# fallBz2.net
KiCad netlist of a schematic drawn in EAGLE
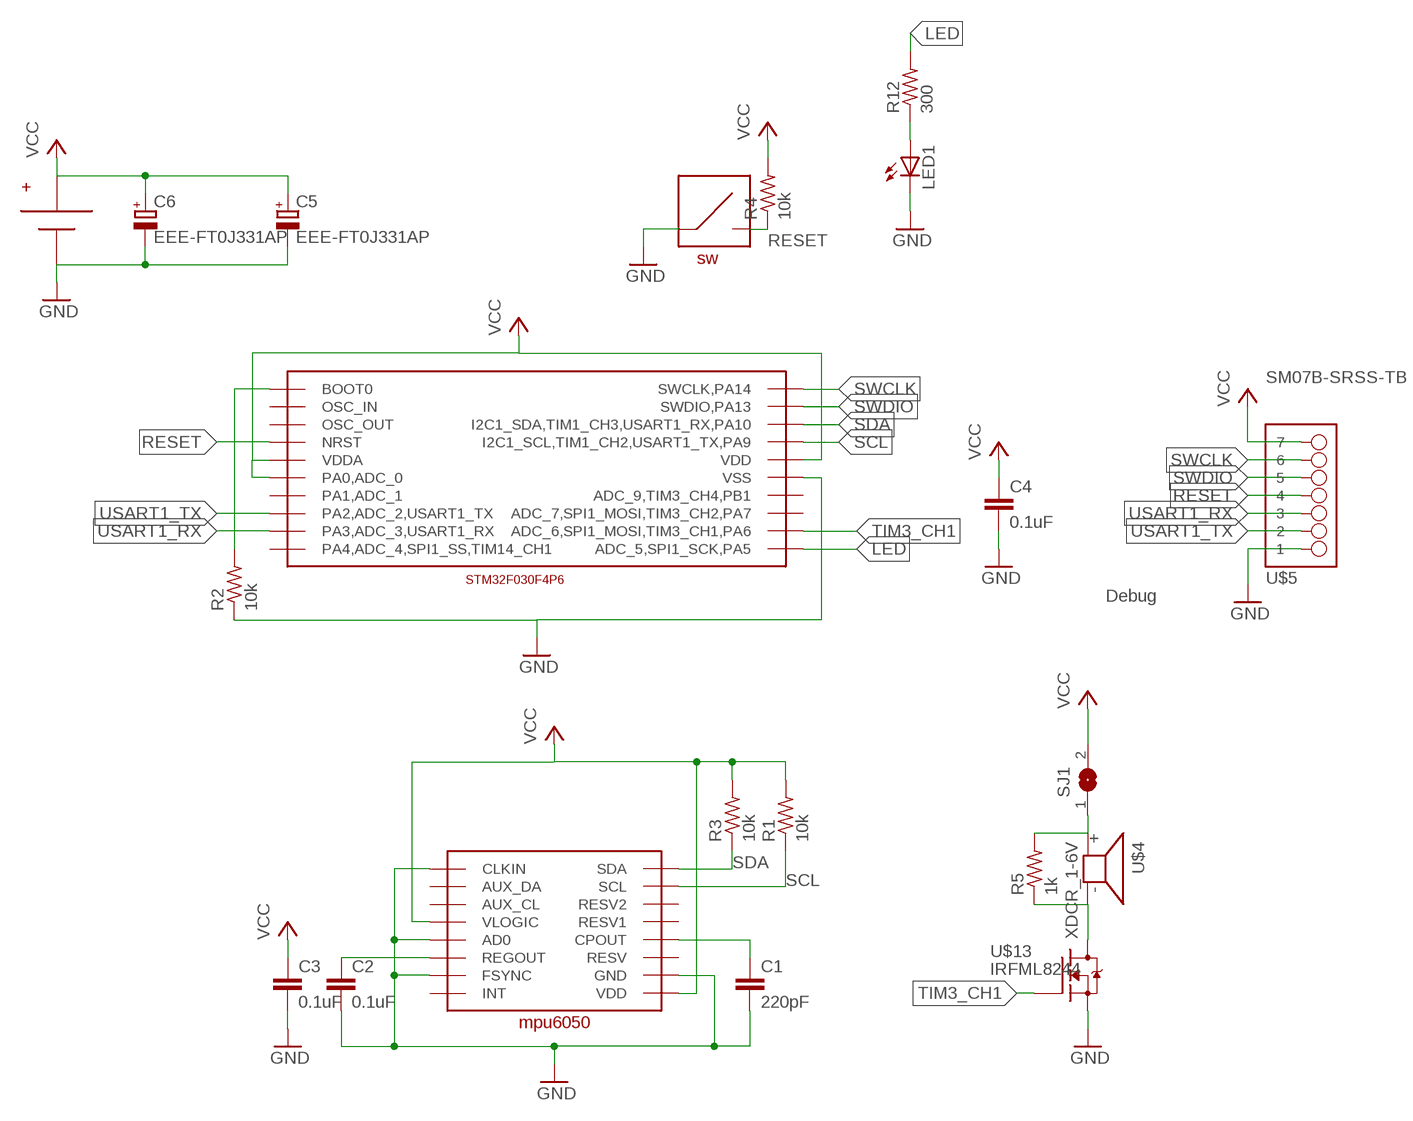
[diagram p0: schematic, sheet 1]

(export (version "E")
  (design (tool "Eeschema 10.0.6"))
  (components
    (comp (ref "C1")
      (value "220pF")
      (footprint "eagle-import:C0603K")
      (libsource (lib "eagle-import") (part "C-EUC0603K"))
    )
    (comp (ref "C2")
      (value "0.1uF")
      (footprint "eagle-import:C0603K")
      (libsource (lib "eagle-import") (part "C-EUC0603K"))
    )
    (comp (ref "C3")
      (value "0.1uF")
      (footprint "eagle-import:C0603K")
      (libsource (lib "eagle-import") (part "C-EUC0603K"))
    )
    (comp (ref "C4")
      (value "0.1uF")
      (footprint "eagle-import:C0603K")
      (libsource (lib "eagle-import") (part "C-EUC0603K"))
    )
    (comp (ref "C5")
      (value "EEE-FT0J331AP")
      (footprint "eagle-import:153CLV-0605")
      (libsource (lib "eagle-import") (part "CPOL-EU153CLV-0605"))
    )
    (comp (ref "C6")
      (value "EEE-FT0J331AP")
      (footprint "eagle-import:153CLV-0605")
      (libsource (lib "eagle-import") (part "CPOL-EU153CLV-0605"))
    )
    (comp (ref "LED1")
      (value "LEDCHIP-LED0603")
      (footprint "eagle-import:CHIP-LED0603")
      (libsource (lib "eagle-import") (part "LEDCHIP-LED0603"))
    )
    (comp (ref "R1")
      (value "10k")
      (footprint "eagle-import:R0603")
      (libsource (lib "eagle-import") (part "R-US_R0603"))
    )
    (comp (ref "R2")
      (value "10k")
      (footprint "eagle-import:R0603")
      (libsource (lib "eagle-import") (part "R-US_R0603"))
    )
    (comp (ref "R3")
      (value "10k")
      (footprint "eagle-import:R0603")
      (libsource (lib "eagle-import") (part "R-US_R0603"))
    )
    (comp (ref "R4")
      (value "10k")
      (footprint "eagle-import:R0603")
      (libsource (lib "eagle-import") (part "R-US_R0603"))
    )
    (comp (ref "R5")
      (value "1k")
      (footprint "eagle-import:R0603")
      (libsource (lib "eagle-import") (part "R-US_R0603"))
    )
    (comp (ref "R12")
      (value "300")
      (footprint "eagle-import:R0603")
      (libsource (lib "eagle-import") (part "R-US_R0603"))
    )
    (comp (ref "SJ1") (value "SJ") (footprint "eagle-import:SJ") (libsource (lib "eagle-import") (part "SJ")))
    (comp (ref "U$1")
      (value "STM-TSSOP20")
      (footprint "eagle-import:STM-TSSOP20")
      (libsource (lib "eagle-import") (part "STM-TSSOP20"))
    )
    (comp (ref "U$2")
      (value "BAT_BK-912")
      (footprint "eagle-import:BAT_BK-912")
      (libsource (lib "eagle-import") (part "BAT_BK-912"))
    )
    (comp (ref "U$3")
      (value "MPU6050")
      (footprint "eagle-import:MPU6050")
      (libsource (lib "eagle-import") (part "MPU6050"))
    )
    (comp (ref "U$4")
      (value "XDCR_1-6V")
      (footprint "eagle-import:XDCR_1-6V")
      (libsource (lib "eagle-import") (part "XDCR_1-6V"))
    )
    (comp (ref "U$5")
      (value "SM07B-SRSS-TB")
      (footprint "eagle-import:SM07B-SRSS-TB")
      (libsource (lib "eagle-import") (part "SM07B-SRSS-TB"))
    )
    (comp (ref "U$7")
      (value "KMT071-NGJ-LHS")
      (footprint "eagle-import:KMT071-NGJ-LHS")
      (libsource (lib "eagle-import") (part "KMT071-NGJ-LHS"))
    )
    (comp (ref "U$13")
      (value "IRFML8244")
      (footprint "eagle-import:SOT23")
      (libsource (lib "eagle-import") (part "IRFML8244"))
    )
  )
  (nets
    (net (code "1") (name "GND") (class "Default")
      (node (ref "C1") (pin "2") (pinfunction "2_2") (pintype "passive"))
      (node (ref "C2") (pin "2") (pinfunction "2_2") (pintype "passive"))
      (node (ref "C3") (pin "2") (pinfunction "2_2") (pintype "passive"))
      (node (ref "C4") (pin "2") (pinfunction "2_2") (pintype "passive"))
      (node (ref "C5") (pin "-") (pinfunction "-_-") (pintype "passive"))
      (node (ref "C6") (pin "-") (pinfunction "-_-") (pintype "passive"))
      (node (ref "LED1") (pin "C") (pinfunction "C_C") (pintype "passive"))
      (node (ref "R2") (pin "1") (pinfunction "1_1") (pintype "passive"))
      (node (ref "U$1") (pin "P$15") (pinfunction "VSS_P$15") (pintype "bidirectional"))
      (node (ref "U$13") (pin "2") (pinfunction "S_2") (pintype "passive"))
      (node (ref "U$2") (pin "MINUS") (pinfunction "MINSU_MINUS") (pintype "bidirectional"))
      (node (ref "U$3") (pin "AD0") (pinfunction "AD0_AD0") (pintype "bidirectional"))
      (node (ref "U$3") (pin "CLKIN") (pinfunction "CLKIN_CLKIN") (pintype "bidirectional"))
      (node (ref "U$3") (pin "FSYNC") (pinfunction "FSYNC_FSYNC") (pintype "bidirectional"))
      (node (ref "U$3") (pin "GND") (pinfunction "GND_GND") (pintype "bidirectional"))
      (node (ref "U$5") (pin "P$1") (pinfunction "1_P$1") (pintype "bidirectional"))
      (node (ref "U$7") (pin "SW0") (pinfunction "P$1_SW0") (pintype "bidirectional"))
      (node (ref "U$7") (pin "SW00") (pinfunction "P$1_SW00") (pintype "bidirectional"))
    )
    (net (code "2") (name "LED") (class "Default")
      (node (ref "R12") (pin "2") (pinfunction "2_2") (pintype "passive"))
      (node (ref "U$1") (pin "P$11") (pinfunction "ADC_5,SPI1_SCK,PA5_P$11") (pintype "bidirectional"))
    )
    (net (code "3") (name "Net-(C1-Pad1)") (class "Default")
      (node (ref "C1") (pin "1") (pinfunction "1_1") (pintype "passive"))
      (node (ref "U$3") (pin "CPOUT") (pinfunction "CPOUT_CPOUT") (pintype "bidirectional"))
    )
    (net (code "4") (name "Net-(C2-Pad1)") (class "Default")
      (node (ref "C2") (pin "1") (pinfunction "1_1") (pintype "passive"))
      (node (ref "U$3") (pin "REGOUT") (pinfunction "REGOUT_REGOUT") (pintype "bidirectional"))
    )
    (net (code "5") (name "Net-(LED1-PadA)") (class "Default")
      (node (ref "LED1") (pin "A") (pinfunction "A_A") (pintype "passive"))
      (node (ref "R12") (pin "1") (pinfunction "1_1") (pintype "passive"))
    )
    (net (code "6") (name "Net-(R5-Pad2)") (class "Default")
      (node (ref "R5") (pin "2") (pinfunction "2_2") (pintype "passive"))
      (node (ref "SJ1") (pin "1") (pinfunction "1_1") (pintype "passive"))
      (node (ref "U$4") (pin "PLUS") (pinfunction "PLUS_PLUS") (pintype "passive"))
    )
    (net (code "7") (name "Net-(U$1-BOOT0)") (class "Default")
      (node (ref "R2") (pin "2") (pinfunction "2_2") (pintype "passive"))
      (node (ref "U$1") (pin "P$1") (pinfunction "BOOT0_P$1") (pintype "bidirectional"))
    )
    (net (code "8") (name "Net-(U$13-D)") (class "Default")
      (node (ref "R5") (pin "1") (pinfunction "1_1") (pintype "passive"))
      (node (ref "U$13") (pin "3") (pinfunction "D_3") (pintype "passive"))
      (node (ref "U$4") (pin "MINUS") (pinfunction "2_MINUS") (pintype "passive"))
    )
    (net (code "9") (name "RESET") (class "Default")
      (node (ref "R4") (pin "1") (pinfunction "1_1") (pintype "passive"))
      (node (ref "U$1") (pin "P$4") (pinfunction "NRST_P$4") (pintype "bidirectional"))
      (node (ref "U$5") (pin "P$4") (pinfunction "4_P$4") (pintype "bidirectional"))
      (node (ref "U$7") (pin "SW1") (pinfunction "P$2_SW1") (pintype "bidirectional"))
      (node (ref "U$7") (pin "SW11") (pinfunction "P$2_SW11") (pintype "bidirectional"))
    )
    (net (code "10") (name "SCL") (class "Default")
      (node (ref "R1") (pin "1") (pinfunction "1_1") (pintype "passive"))
      (node (ref "U$1") (pin "P$17") (pinfunction "I2C1_SCL,TIM1_CH2,USART1_TX,PA9_P$17") (pintype "bidirectional"))
      (node (ref "U$3") (pin "SCL") (pinfunction "SCL_SCL") (pintype "bidirectional"))
    )
    (net (code "11") (name "SDA") (class "Default")
      (node (ref "R3") (pin "1") (pinfunction "1_1") (pintype "passive"))
      (node (ref "U$1") (pin "P$18") (pinfunction "I2C1_SDA,TIM1_CH3,USART1_RX,PA10_P$18") (pintype "bidirectional"))
      (node (ref "U$3") (pin "SDA") (pinfunction "SDA_SDA") (pintype "bidirectional"))
    )
    (net (code "12") (name "SWCLK") (class "Default")
      (node (ref "U$1") (pin "P$20") (pinfunction "SWCLK,PA14_P$20") (pintype "bidirectional"))
      (node (ref "U$5") (pin "P$6") (pinfunction "6_P$6") (pintype "bidirectional"))
    )
    (net (code "13") (name "SWDIO") (class "Default")
      (node (ref "U$1") (pin "P$19") (pinfunction "SWDIO,PA13_P$19") (pintype "bidirectional"))
      (node (ref "U$5") (pin "P$5") (pinfunction "5_P$5") (pintype "bidirectional"))
    )
    (net (code "14") (name "TIM3_CH1") (class "Default")
      (node (ref "U$1") (pin "P$12") (pinfunction "ADC_6,SPI1_MOSI,TIM3_CH1,PA6_P$12") (pintype "bidirectional"))
      (node (ref "U$13") (pin "1") (pinfunction "G_1") (pintype "passive"))
    )
    (net (code "15") (name "USART1_RX") (class "Default")
      (node (ref "U$1") (pin "P$9") (pinfunction "PA3,ADC_3,USART1_RX_P$9") (pintype "bidirectional"))
      (node (ref "U$5") (pin "P$3") (pinfunction "3_P$3") (pintype "bidirectional"))
    )
    (net (code "16") (name "USART1_TX") (class "Default")
      (node (ref "U$1") (pin "P$8") (pinfunction "PA2,ADC_2,USART1_TX_P$8") (pintype "bidirectional"))
      (node (ref "U$5") (pin "P$2") (pinfunction "2_P$2") (pintype "bidirectional"))
    )
    (net (code "17") (name "VCC") (class "Default")
      (node (ref "C3") (pin "1") (pinfunction "1_1") (pintype "passive"))
      (node (ref "C4") (pin "1") (pinfunction "1_1") (pintype "passive"))
      (node (ref "C5") (pin "+") (pinfunction "+_+") (pintype "passive"))
      (node (ref "C6") (pin "+") (pinfunction "+_+") (pintype "passive"))
      (node (ref "R1") (pin "2") (pinfunction "2_2") (pintype "passive"))
      (node (ref "R3") (pin "2") (pinfunction "2_2") (pintype "passive"))
      (node (ref "R4") (pin "2") (pinfunction "2_2") (pintype "passive"))
      (node (ref "SJ1") (pin "2") (pinfunction "2_2") (pintype "passive"))
      (node (ref "U$1") (pin "P$16") (pinfunction "VDD_P$16") (pintype "bidirectional"))
      (node (ref "U$1") (pin "P$5") (pinfunction "VDDA_P$5") (pintype "bidirectional"))
      (node (ref "U$1") (pin "P$6") (pinfunction "PA0,ADC_0_P$6") (pintype "bidirectional"))
      (node (ref "U$2") (pin "P$1") (pinfunction "PLUS_P$1") (pintype "bidirectional"))
      (node (ref "U$2") (pin "P$2") (pinfunction "PLUS_P$2") (pintype "bidirectional"))
      (node (ref "U$3") (pin "VDD") (pinfunction "VDD_VDD") (pintype "bidirectional"))
      (node (ref "U$3") (pin "VLOGIC") (pinfunction "VLOGIC_VLOGIC") (pintype "bidirectional"))
      (node (ref "U$5") (pin "P$7") (pinfunction "7_P$7") (pintype "bidirectional"))
    )
    (net (code "18") (name "unconnected-(U$1-ADC_7,SPI1_MOSI,TIM3_CH2,PA7-PadP$13)") (class "Default")
      (node (ref "U$1") (pin "P$13") (pinfunction "ADC_7,SPI1_MOSI,TIM3_CH2,PA7_P$13") (pintype "bidirectional"))
    )
    (net (code "19") (name "unconnected-(U$1-ADC_9,TIM3_CH4,PB1-PadP$14)") (class "Default")
      (node (ref "U$1") (pin "P$14") (pinfunction "ADC_9,TIM3_CH4,PB1_P$14") (pintype "bidirectional"))
    )
    (net (code "20") (name "unconnected-(U$1-OSC_IN-PadP$2)") (class "Default")
      (node (ref "U$1") (pin "P$2") (pinfunction "OSC_IN_P$2") (pintype "bidirectional"))
    )
    (net (code "21") (name "unconnected-(U$1-OSC_OUT-PadP$3)") (class "Default")
      (node (ref "U$1") (pin "P$3") (pinfunction "OSC_OUT_P$3") (pintype "bidirectional"))
    )
    (net (code "22") (name "unconnected-(U$1-PA1,ADC_1-PadP$7)") (class "Default")
      (node (ref "U$1") (pin "P$7") (pinfunction "PA1,ADC_1_P$7") (pintype "bidirectional"))
    )
    (net (code "23") (name "unconnected-(U$1-PA4,ADC_4,SPI1_SS,TIM14_CH1-PadP$10)") (class "Default")
      (node (ref "U$1") (pin "P$10") (pinfunction "PA4,ADC_4,SPI1_SS,TIM14_CH1_P$10") (pintype "bidirectional"))
    )
    (net (code "24") (name "unconnected-(U$3-PadAUX_CL)") (class "Default")
      (node (ref "U$3") (pin "AUX_CL") (pinfunction "AUX_CL_AUX_CL") (pintype "bidirectional"))
    )
    (net (code "25") (name "unconnected-(U$3-PadAUX_DA)") (class "Default")
      (node (ref "U$3") (pin "AUX_DA") (pinfunction "AUX_DA_AUX_DA") (pintype "bidirectional"))
    )
    (net (code "26") (name "unconnected-(U$3-PadINT)") (class "Default")
      (node (ref "U$3") (pin "INT") (pinfunction "INT_INT") (pintype "bidirectional"))
    )
    (net (code "27") (name "unconnected-(U$3-PadRESV)") (class "Default")
      (node (ref "U$3") (pin "RESV") (pinfunction "RESV_RESV") (pintype "bidirectional"))
    )
    (net (code "28") (name "unconnected-(U$3-PadRESV1)") (class "Default")
      (node (ref "U$3") (pin "RESV1") (pinfunction "RESV1_RESV1") (pintype "bidirectional"))
    )
    (net (code "29") (name "unconnected-(U$3-PadRESV2)") (class "Default")
      (node (ref "U$3") (pin "RESV2") (pinfunction "RESV2_RESV2") (pintype "bidirectional"))
    )
  )
)
